# RS485.net
KiCad netlist of a schematic drawn in Altium Designer
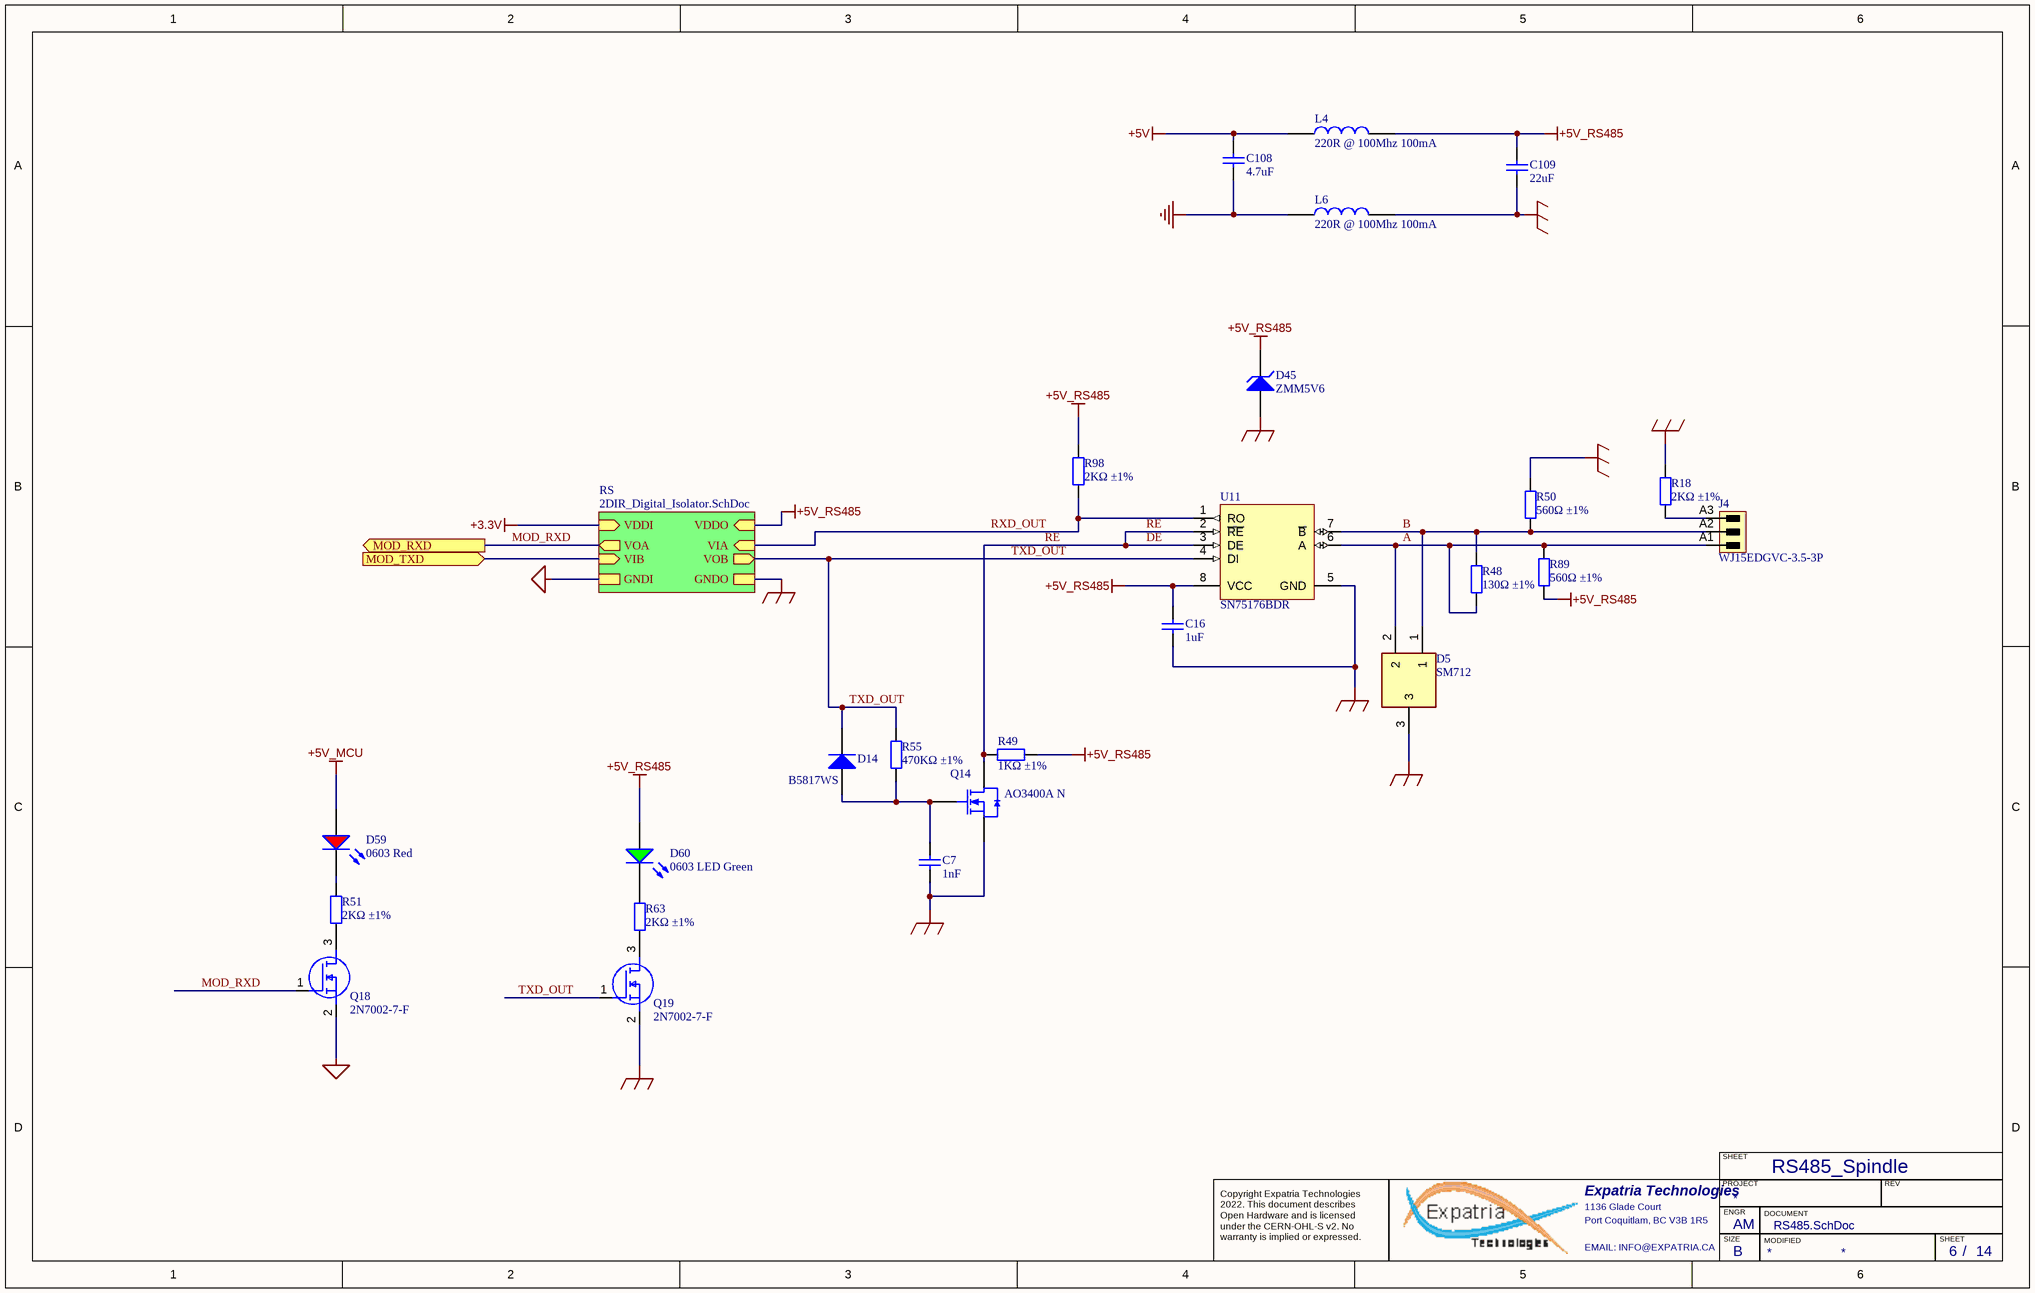
[diagram p0: RS485.SchDoc]

(export (version "E")
  (design (tool "Eeschema 10.0.6"))
  (components
    (comp (ref "C7")
      (value "1nF")
      (footprint "0603_C")
      (description "Chip capacitors")
      (fields
        (field (name "MANUFACTURER") "Samsung Electro-Mechanics")
        (field (name "PARTNUMBER") "CL10B102KB8NNNC")
      )
      (libsource (lib "Cap") (part "0603 1nF (102) 10% 50V"))
    )
    (comp (ref "C16")
      (value "1uF")
      (footprint "0603_C")
      (description "Chip capacitors")
      (fields
        (field (name "MANUFACTURER") "Samsung Electro-Mechanics")
        (field (name "PARTNUMBER") "CL10A105KB8NNNC")
      )
      (libsource (lib "Cap") (part "0603 1uF (105) 10% 50V"))
    )
    (comp (ref "C108")
      (value "4.7uF")
      (footprint "0805_C")
      (description "Chip capacitors")
      (fields
        (field (name "MANUFACTURER") "Samsung Electro-Mechanics")
        (field (name "PARTNUMBER") "CL21A475KAQNNNE")
      )
      (libsource (lib "Cap") (part "0805 4.7uF (475) 10% 25V"))
    )
    (comp (ref "C109")
      (value "22uF")
      (footprint "0805_C")
      (description "Chip capacitors")
      (fields
        (field (name "MANUFACTURER") "Samsung Electro-Mechanics")
        (field (name "PARTNUMBER") "CL21A226MAQNNNE")
      )
      (libsource (lib "Cap") (part "0805 22uF (226) 20% 25V"))
    )
    (comp (ref "D5")
      (value "SM712")
      (footprint "SamacSys:SOT95P230X117-3N")
      (description "Bidirectional 12V (Max), 7V (Max) 7.5V / 13.3V 10V / 20V 12A(8/20us) SOT-23-3 TVS RoHS")
      (libsource (lib "*") (part "CDSOT23-SM712"))
    )
    (comp (ref "D14")
      (value "B5817WS")
      (footprint "SOD-323")
      (description "20V 750mV@3A 1A SOD-323 Schottky Barrier Diodes (SBD) ROHS")
      (libsource (lib "Diode") (part "SOD-123 B5819W  SL"))
    )
    (comp (ref "D45")
      (value "ZMM5V6")
      (footprint "LL-34")
      (description "500mW - 0.1uA @ 1V 5.6V LL-34 Zener Diodes ROHS")
      (libsource (lib "Zener") (part "LL-34 ZMM5V6"))
    )
    (comp (ref "D59")
      (value "0603 Red")
      (footprint "0603_LED_S1")
      (fields
        (field (name "MANUFACTURER") "Everlight Elec")
        (field (name "MANUFACTURER PART NUMBER") "19-213SURC/S530-A3/TR8")
      )
      (libsource (lib "Sienci_Labs") (part "19-213SURC/S530-A3/TR8"))
    )
    (comp (ref "D60")
      (value "0603 LED Green")
      (footprint "0603_LED_S1")
      (fields
        (field (name "MANUFACTURER PART NUMBER") "19-217/GHC-YR1S2/3T")
        (field (name "MANUFACTURER") "Everlight Elec")
      )
      (libsource (lib "Sienci_Labs") (part "19-217/GHC-YR1S2/3T"))
    )
    (comp (ref "J4")
      (value "WJ15EDGVC-3.5-3P")
      (footprint "691321100003 - 3.5mm  3p")
      (fields (field (name "MANUFACTURER") "Ningbo Kangnex Elec"))
      (libsource (lib "Universal_CNC_Breakout") (part "3.5mm Terminal Header 3p"))
    )
    (comp (ref "L4")
      (value "220R @ 100Mhz 100mA")
      (footprint "0402_L")
      (description "Ferrite Bead")
      (libsource (lib "FBEAD") (part "0402 220R@100Mhz 0.1A"))
    )
    (comp (ref "L6")
      (value "220R @ 100Mhz 100mA")
      (footprint "0402_L")
      (description "Ferrite Bead")
      (libsource (lib "FBEAD") (part "0402 220R@100Mhz 0.1A"))
    )
    (comp (ref "Q14")
      (value "AO3400A N")
      (footprint "SOT-23-3L")
      (description "MOS(场效应管)")
      (libsource (lib "MOS") (part "AO3400A N道沟 X0YV1T SOT-23"))
    )
    (comp (ref "Q18")
      (value "2N7002-7-F")
      (footprint "SOT-23(SOT-23-3)")
      (description "60V 115mA 7.5Ω@5V,50mA 370mW N Channel SOT-23 MOSFETs ROHS")
      (fields (field (name "MANUFACTURER") "Diodes Inc.") (field (name "MOUSER PART NUMBER") "621-2N7002-F"))
      (libsource (lib "Sienci_Labs") (part "2N7002-7-F"))
    )
    (comp (ref "Q19")
      (value "2N7002-7-F")
      (footprint "SOT-23(SOT-23-3)")
      (description "60V 115mA 7.5Ω@5V,50mA 370mW N Channel SOT-23 MOSFETs ROHS")
      (fields (field (name "MANUFACTURER") "Diodes Inc.") (field (name "MOUSER PART NUMBER") "621-2N7002-F"))
      (libsource (lib "Sienci_Labs") (part "2N7002-7-F"))
    )
    (comp (ref "R18")
      (value "2KΩ ±1%")
      (footprint "0603_R")
      (description "Chip resistor")
      (fields (field (name "MANUFACTURER") "Uniroyal Elec") (field (name "PARTNUMBER") "0603WAF2001T5E"))
      (libsource (lib "RES") (part "0603 2K (2001) 1%"))
    )
    (comp (ref "R48")
      (value "130Ω ±1%")
      (footprint "0603_R")
      (description "Chip resistor")
      (fields (field (name "MANUFACTURER") "Uniroyal Elec") (field (name "PARTNUMBER") "0603WAF1300T5E"))
      (libsource (lib "RES") (part "0603 130R (1300) 1%"))
    )
    (comp (ref "R49")
      (value "1KΩ ±1%")
      (footprint "0603_R")
      (description "Chip resistor")
      (fields (field (name "MANUFACTURER") "Uniroyal Elec") (field (name "PARTNUMBER") "0603WAF1001T5E"))
      (libsource (lib "RES") (part "0603 1K (1001) 1%"))
    )
    (comp (ref "R50")
      (value "560Ω ±1%")
      (footprint "0603_R")
      (description "Chip resistor")
      (fields (field (name "MANUFACTURER") "Uniroyal Elec") (field (name "PARTNUMBER") "0603WAF5600T5E"))
      (libsource (lib "RES") (part "0603 560R (5600) 1%"))
    )
    (comp (ref "R51")
      (value "2KΩ ±1%")
      (footprint "0402_R")
      (description "Chip resistor")
      (fields
        (field (name "MANUFACTURER") "Uniroyal Elec")
        (field (name "MANUFACTURER PART NUMBER") "0402WGF2001TCE")
      )
      (libsource (lib "RES") (part "0402 2K (2001) 1%"))
    )
    (comp (ref "R55")
      (value "470KΩ ±1%")
      (footprint "0603_R")
      (description "Chip resistor")
      (fields (field (name "MANUFACTURER") "Uniroyal Elec") (field (name "PARTNUMBER") "0603WAF4703T5E"))
      (libsource (lib "RES") (part "0603 470K (4703) 1%"))
    )
    (comp (ref "R63")
      (value "2KΩ ±1%")
      (footprint "0402_R")
      (description "Chip resistor")
      (fields
        (field (name "MANUFACTURER") "Uniroyal Elec")
        (field (name "MANUFACTURER PART NUMBER") "0402WGF2001TCE")
      )
      (libsource (lib "RES") (part "0402 2K (2001) 1%"))
    )
    (comp (ref "R89")
      (value "560Ω ±1%")
      (footprint "0603_R")
      (description "Chip resistor")
      (fields (field (name "MANUFACTURER") "Uniroyal Elec") (field (name "PARTNUMBER") "0603WAF5600T5E"))
      (libsource (lib "RES") (part "0603 560R (5600) 1%"))
    )
    (comp (ref "R98")
      (value "2KΩ ±1%")
      (footprint "0603_R")
      (description "Chip resistor")
      (fields (field (name "MANUFACTURER") "Uniroyal Elec") (field (name "PARTNUMBER") "0603WAF2001T5E"))
      (libsource (lib "") (part "0603 2K (2001) 1%_1"))
    )
    (comp (ref "U11")
      (value "SN75176BDR")
      (footprint "SOIC-8_150mil")
      (description "RS-485/RS-422")
      (libsource (lib "IC") (part "SN75176BDR_[C7063]"))
    )
  )
  (nets
    (net (code "2") (name "+5V") (class "Default")
      (node (ref "C108") (pin "2") (pinfunction "2_2") (pintype "passive"))
      (node (ref "L4") (pin "1") (pinfunction "1_1") (pintype "passive"))
    )
    (net (code "3") (name "+5V_MCU") (class "Default")
      (node (ref "D59") (pin "A") (pinfunction "A_A") (pintype "passive"))
    )
    (net (code "4") (name "+5V_RS485") (class "Default")
      (node (ref "C109") (pin "2") (pinfunction "2_2") (pintype "passive"))
      (node (ref "C16") (pin "2") (pinfunction "2_2") (pintype "passive"))
      (node (ref "D45") (pin "2") (pinfunction "K_2") (pintype "passive"))
      (node (ref "D60") (pin "A") (pinfunction "A_A") (pintype "passive"))
      (node (ref "L4") (pin "2") (pinfunction "2_2") (pintype "passive"))
      (node (ref "R49") (pin "1") (pinfunction "1_1") (pintype "passive"))
      (node (ref "R89") (pin "2") (pinfunction "2_2") (pintype "passive"))
      (node (ref "R98") (pin "2") (pinfunction "2_2") (pintype "passive"))
      (node (ref "U11") (pin "8") (pinfunction "VCC_8") (pintype "power_in"))
    )
    (net (code "5") (name "/A") (class "Default")
      (node (ref "D5") (pin "2") (pinfunction "2_2") (pintype "passive"))
      (node (ref "J4") (pin "A1") (pinfunction "A1_A1") (pintype "passive"))
      (node (ref "R48") (pin "1") (pinfunction "1_1") (pintype "passive"))
      (node (ref "R89") (pin "1") (pinfunction "1_1") (pintype "passive"))
      (node (ref "U11") (pin "6") (pinfunction "A_6") (pintype "bidirectional"))
    )
    (net (code "6") (name "/B") (class "Default")
      (node (ref "D5") (pin "1") (pinfunction "1_1") (pintype "passive"))
      (node (ref "J4") (pin "A2") (pinfunction "A2_A2") (pintype "passive"))
      (node (ref "R48") (pin "2") (pinfunction "2_2") (pintype "passive"))
      (node (ref "R50") (pin "2") (pinfunction "2_2") (pintype "passive"))
      (node (ref "U11") (pin "7") (pinfunction "~{B}_7") (pintype "bidirectional"))
    )
    (net (code "7") (name "/DE") (class "Default")
      (node (ref "Q14") (pin "3") (pinfunction "D_3") (pintype "passive"))
      (node (ref "R49") (pin "2") (pinfunction "2_2") (pintype "passive"))
      (node (ref "U11") (pin "2") (pinfunction "~{RE}_2") (pintype "input"))
      (node (ref "U11") (pin "3") (pinfunction "DE_3") (pintype "input"))
    )
    (net (code "8") (name "/MOD_RXD") (class "Default")
      (node (ref "Q18") (pin "1") (pinfunction "G_1") (pintype "passive"))
    )
    (net (code "10") (name "/RXD_OUT") (class "Default")
      (node (ref "R98") (pin "1") (pinfunction "1_1") (pintype "passive"))
      (node (ref "U11") (pin "1") (pinfunction "RO_1") (pintype "output"))
    )
    (net (code "11") (name "/TXD_OUT") (class "Default")
      (node (ref "D14") (pin "2") (pinfunction "K_2") (pintype "passive"))
      (node (ref "Q19") (pin "1") (pinfunction "G_1") (pintype "passive"))
      (node (ref "R55") (pin "1") (pinfunction "1_1") (pintype "passive"))
      (node (ref "U11") (pin "4") (pinfunction "DI_4") (pintype "input"))
    )
    (net (code "12") (name "GND") (class "Default")
      (node (ref "C108") (pin "1") (pinfunction "1_1") (pintype "passive"))
      (node (ref "L6") (pin "1") (pinfunction "1_1") (pintype "passive"))
    )
    (net (code "13") (name "MCU_GND") (class "Default")
      (node (ref "Q18") (pin "2") (pinfunction "S_2") (pintype "passive"))
    )
    (net (code "14") (name "MOD_GND") (class "Default")
      (node (ref "C109") (pin "1") (pinfunction "1_1") (pintype "passive"))
      (node (ref "C16") (pin "1") (pinfunction "1_1") (pintype "passive"))
      (node (ref "C7") (pin "2") (pinfunction "2_2") (pintype "passive"))
      (node (ref "D45") (pin "1") (pinfunction "A_1") (pintype "passive"))
      (node (ref "D5") (pin "3") (pinfunction "3_3") (pintype "passive"))
      (node (ref "L6") (pin "2") (pinfunction "2_2") (pintype "passive"))
      (node (ref "Q14") (pin "2") (pinfunction "S_2") (pintype "passive"))
      (node (ref "Q19") (pin "2") (pinfunction "S_2") (pintype "passive"))
      (node (ref "R18") (pin "1") (pinfunction "1_1") (pintype "passive"))
      (node (ref "R50") (pin "1") (pinfunction "1_1") (pintype "passive"))
      (node (ref "U11") (pin "5") (pinfunction "GND_5") (pintype "power_in"))
    )
    (net (code "15") (name "Net-(D14-A)") (class "Default")
      (node (ref "C7") (pin "1") (pinfunction "1_1") (pintype "passive"))
      (node (ref "D14") (pin "1") (pinfunction "A_1") (pintype "passive"))
      (node (ref "Q14") (pin "1") (pinfunction "G_1") (pintype "passive"))
      (node (ref "R55") (pin "2") (pinfunction "2_2") (pintype "passive"))
    )
    (net (code "16") (name "Net-(D59-PadK)") (class "Default")
      (node (ref "D59") (pin "K") (pinfunction "K_K") (pintype "passive"))
      (node (ref "R51") (pin "2") (pinfunction "2_2") (pintype "passive"))
    )
    (net (code "17") (name "Net-(D60-PadK)") (class "Default")
      (node (ref "D60") (pin "K") (pinfunction "K_K") (pintype "passive"))
      (node (ref "R63") (pin "2") (pinfunction "2_2") (pintype "passive"))
    )
    (net (code "18") (name "Net-(J4-PadA3)") (class "Default")
      (node (ref "J4") (pin "A3") (pinfunction "A3_A3") (pintype "passive"))
      (node (ref "R18") (pin "2") (pinfunction "2_2") (pintype "passive"))
    )
    (net (code "19") (name "Net-(Q18-D)") (class "Default")
      (node (ref "Q18") (pin "3") (pinfunction "D_3") (pintype "passive"))
      (node (ref "R51") (pin "1") (pinfunction "1_1") (pintype "passive"))
    )
    (net (code "20") (name "Net-(Q19-D)") (class "Default")
      (node (ref "Q19") (pin "3") (pinfunction "D_3") (pintype "passive"))
      (node (ref "R63") (pin "1") (pinfunction "1_1") (pintype "passive"))
    )
  )
)
